# optoControl.net
KiCad netlist of a schematic drawn in Altium Designer
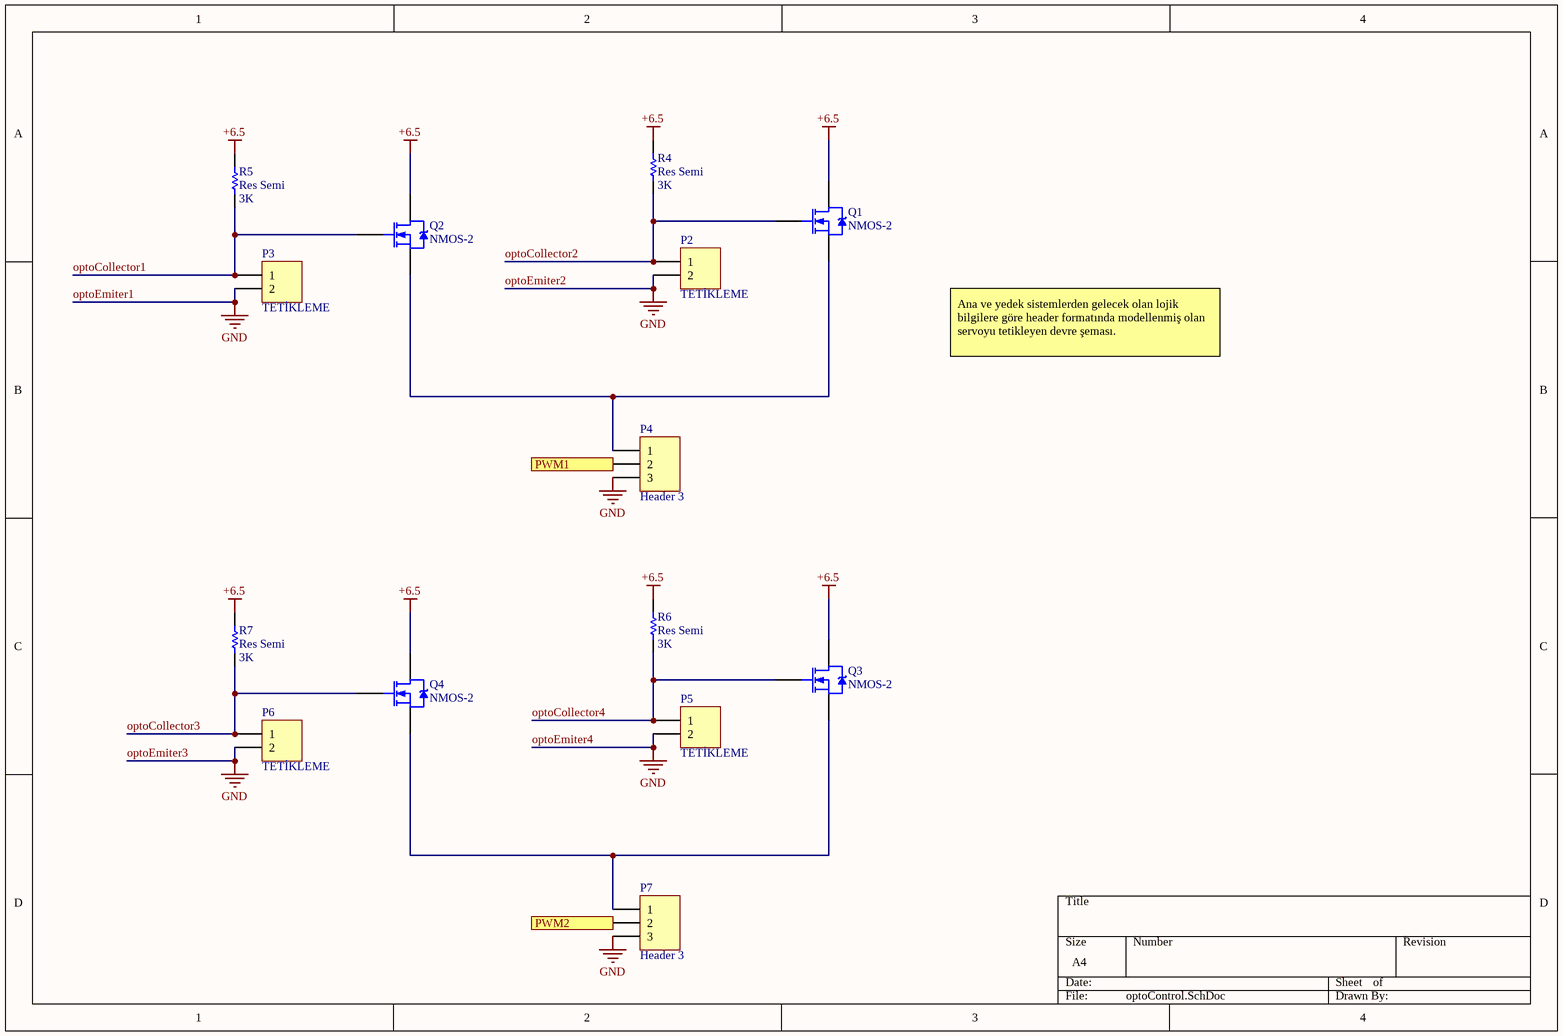
[diagram p0: optoControl.SchDoc]

(export (version "E")
  (design (tool "Eeschema 10.0.6"))
  (components
    (comp (ref "P2")
      (value "TETİKLEME")
      (footprint "HDR1X2")
      (description "Header, 2-Pin")
      (fields (field (name "PUBLISHER") "Altium Limited"))
      (libsource (lib "Miscellaneous Connectors") (part "Header 2"))
    )
    (comp (ref "P3")
      (value "TETİKLEME")
      (footprint "HDR1X2")
      (description "Header, 2-Pin")
      (fields (field (name "PUBLISHER") "Altium Limited"))
      (libsource (lib "Miscellaneous Connectors") (part "Header 2"))
    )
    (comp (ref "P4")
      (value "Header 3")
      (footprint "HDR1X3")
      (description "Header, 3-Pin")
      (fields (field (name "PUBLISHER") "Altium Limited"))
      (libsource (lib "Miscellaneous Connectors") (part "Header 3"))
    )
    (comp (ref "P5")
      (value "TETİKLEME")
      (footprint "HDR1X2")
      (description "Header, 2-Pin")
      (fields (field (name "PUBLISHER") "Altium Limited"))
      (libsource (lib "Miscellaneous Connectors") (part "Header 2"))
    )
    (comp (ref "P6")
      (value "TETİKLEME")
      (footprint "HDR1X2")
      (description "Header, 2-Pin")
      (fields (field (name "PUBLISHER") "Altium Limited"))
      (libsource (lib "Miscellaneous Connectors") (part "Header 2"))
    )
    (comp (ref "P7")
      (value "Header 3")
      (footprint "HDR1X3")
      (description "Header, 3-Pin")
      (fields (field (name "PUBLISHER") "Altium Limited"))
      (libsource (lib "Miscellaneous Connectors") (part "Header 3"))
    )
    (comp (ref "Q1")
      (value "NMOS-2")
      (footprint "TO-220AB")
      (description "N-Channel Power MOSFET")
      (fields (field (name "PUBLISHER") "Altium Limited"))
      (libsource (lib "Miscellaneous Devices") (part "NMOS-2"))
    )
    (comp (ref "Q2")
      (value "NMOS-2")
      (footprint "TO-220AB")
      (description "N-Channel Power MOSFET")
      (fields (field (name "PUBLISHER") "Altium Limited"))
      (libsource (lib "Miscellaneous Devices") (part "NMOS-2"))
    )
    (comp (ref "Q3")
      (value "NMOS-2")
      (footprint "TO-220AB")
      (description "N-Channel Power MOSFET")
      (fields (field (name "PUBLISHER") "Altium Limited"))
      (libsource (lib "Miscellaneous Devices") (part "NMOS-2"))
    )
    (comp (ref "Q4")
      (value "NMOS-2")
      (footprint "TO-220AB")
      (description "N-Channel Power MOSFET")
      (fields (field (name "PUBLISHER") "Altium Limited"))
      (libsource (lib "Miscellaneous Devices") (part "NMOS-2"))
    )
    (comp (ref "R4")
      (value "Res Semi")
      (footprint "AXIAL-0.5")
      (description "Semiconductor Resistor")
      (fields (field (name "ALTIUM_VALUE") "3K") (field (name "PUBLISHER") "Altium Limited"))
      (libsource (lib "Miscellaneous Devices") (part "Res Semi"))
    )
    (comp (ref "R5")
      (value "Res Semi")
      (footprint "AXIAL-0.5")
      (description "Semiconductor Resistor")
      (fields (field (name "ALTIUM_VALUE") "3K") (field (name "PUBLISHER") "Altium Limited"))
      (libsource (lib "Miscellaneous Devices") (part "Res Semi"))
    )
    (comp (ref "R6")
      (value "Res Semi")
      (footprint "AXIAL-0.5")
      (description "Semiconductor Resistor")
      (fields (field (name "ALTIUM_VALUE") "3K") (field (name "PUBLISHER") "Altium Limited"))
      (libsource (lib "Miscellaneous Devices") (part "Res Semi"))
    )
    (comp (ref "R7")
      (value "Res Semi")
      (footprint "AXIAL-0.5")
      (description "Semiconductor Resistor")
      (fields (field (name "ALTIUM_VALUE") "3K") (field (name "PUBLISHER") "Altium Limited"))
      (libsource (lib "Miscellaneous Devices") (part "Res Semi"))
    )
  )
  (nets
    (net (code "1") (name "+6.5") (class "Default")
      (node (ref "Q1") (pin "2") (pinfunction "D_2") (pintype "passive"))
      (node (ref "Q2") (pin "2") (pinfunction "D_2") (pintype "passive"))
      (node (ref "Q3") (pin "2") (pinfunction "D_2") (pintype "passive"))
      (node (ref "Q4") (pin "2") (pinfunction "D_2") (pintype "passive"))
      (node (ref "R4") (pin "2") (pinfunction "2_2") (pintype "passive"))
      (node (ref "R5") (pin "2") (pinfunction "2_2") (pintype "passive"))
      (node (ref "R6") (pin "2") (pinfunction "2_2") (pintype "passive"))
      (node (ref "R7") (pin "2") (pinfunction "2_2") (pintype "passive"))
    )
    (net (code "2") (name "/PWM1") (class "Default")
      (node (ref "P4") (pin "2") (pinfunction "2_2") (pintype "passive"))
    )
    (net (code "3") (name "/PWM2") (class "Default")
      (node (ref "P7") (pin "2") (pinfunction "2_2") (pintype "passive"))
    )
    (net (code "4") (name "/optoCollector1") (class "Default")
      (node (ref "P3") (pin "1") (pinfunction "1_1") (pintype "passive"))
      (node (ref "Q2") (pin "1") (pinfunction "G_1") (pintype "passive"))
      (node (ref "R5") (pin "1") (pinfunction "1_1") (pintype "passive"))
    )
    (net (code "5") (name "/optoCollector2") (class "Default")
      (node (ref "P2") (pin "1") (pinfunction "1_1") (pintype "passive"))
      (node (ref "Q1") (pin "1") (pinfunction "G_1") (pintype "passive"))
      (node (ref "R4") (pin "1") (pinfunction "1_1") (pintype "passive"))
    )
    (net (code "6") (name "/optoCollector3") (class "Default")
      (node (ref "P6") (pin "1") (pinfunction "1_1") (pintype "passive"))
      (node (ref "Q4") (pin "1") (pinfunction "G_1") (pintype "passive"))
      (node (ref "R7") (pin "1") (pinfunction "1_1") (pintype "passive"))
    )
    (net (code "7") (name "/optoCollector4") (class "Default")
      (node (ref "P5") (pin "1") (pinfunction "1_1") (pintype "passive"))
      (node (ref "Q3") (pin "1") (pinfunction "G_1") (pintype "passive"))
      (node (ref "R6") (pin "1") (pinfunction "1_1") (pintype "passive"))
    )
    (net (code "8") (name "GND") (class "Default")
      (node (ref "P2") (pin "2") (pinfunction "2_2") (pintype "passive"))
      (node (ref "P3") (pin "2") (pinfunction "2_2") (pintype "passive"))
      (node (ref "P4") (pin "3") (pinfunction "3_3") (pintype "passive"))
      (node (ref "P5") (pin "2") (pinfunction "2_2") (pintype "passive"))
      (node (ref "P6") (pin "2") (pinfunction "2_2") (pintype "passive"))
      (node (ref "P7") (pin "3") (pinfunction "3_3") (pintype "passive"))
    )
    (net (code "9") (name "Net-(Q1-S)") (class "Default")
      (node (ref "P4") (pin "1") (pinfunction "1_1") (pintype "passive"))
      (node (ref "Q1") (pin "3") (pinfunction "S_3") (pintype "passive"))
      (node (ref "Q2") (pin "3") (pinfunction "S_3") (pintype "passive"))
    )
    (net (code "10") (name "Net-(Q3-S)") (class "Default")
      (node (ref "P7") (pin "1") (pinfunction "1_1") (pintype "passive"))
      (node (ref "Q3") (pin "3") (pinfunction "S_3") (pintype "passive"))
      (node (ref "Q4") (pin "3") (pinfunction "S_3") (pintype "passive"))
    )
  )
)
